# design.net
KiCad netlist of a schematic drawn in EasyEDA Pro
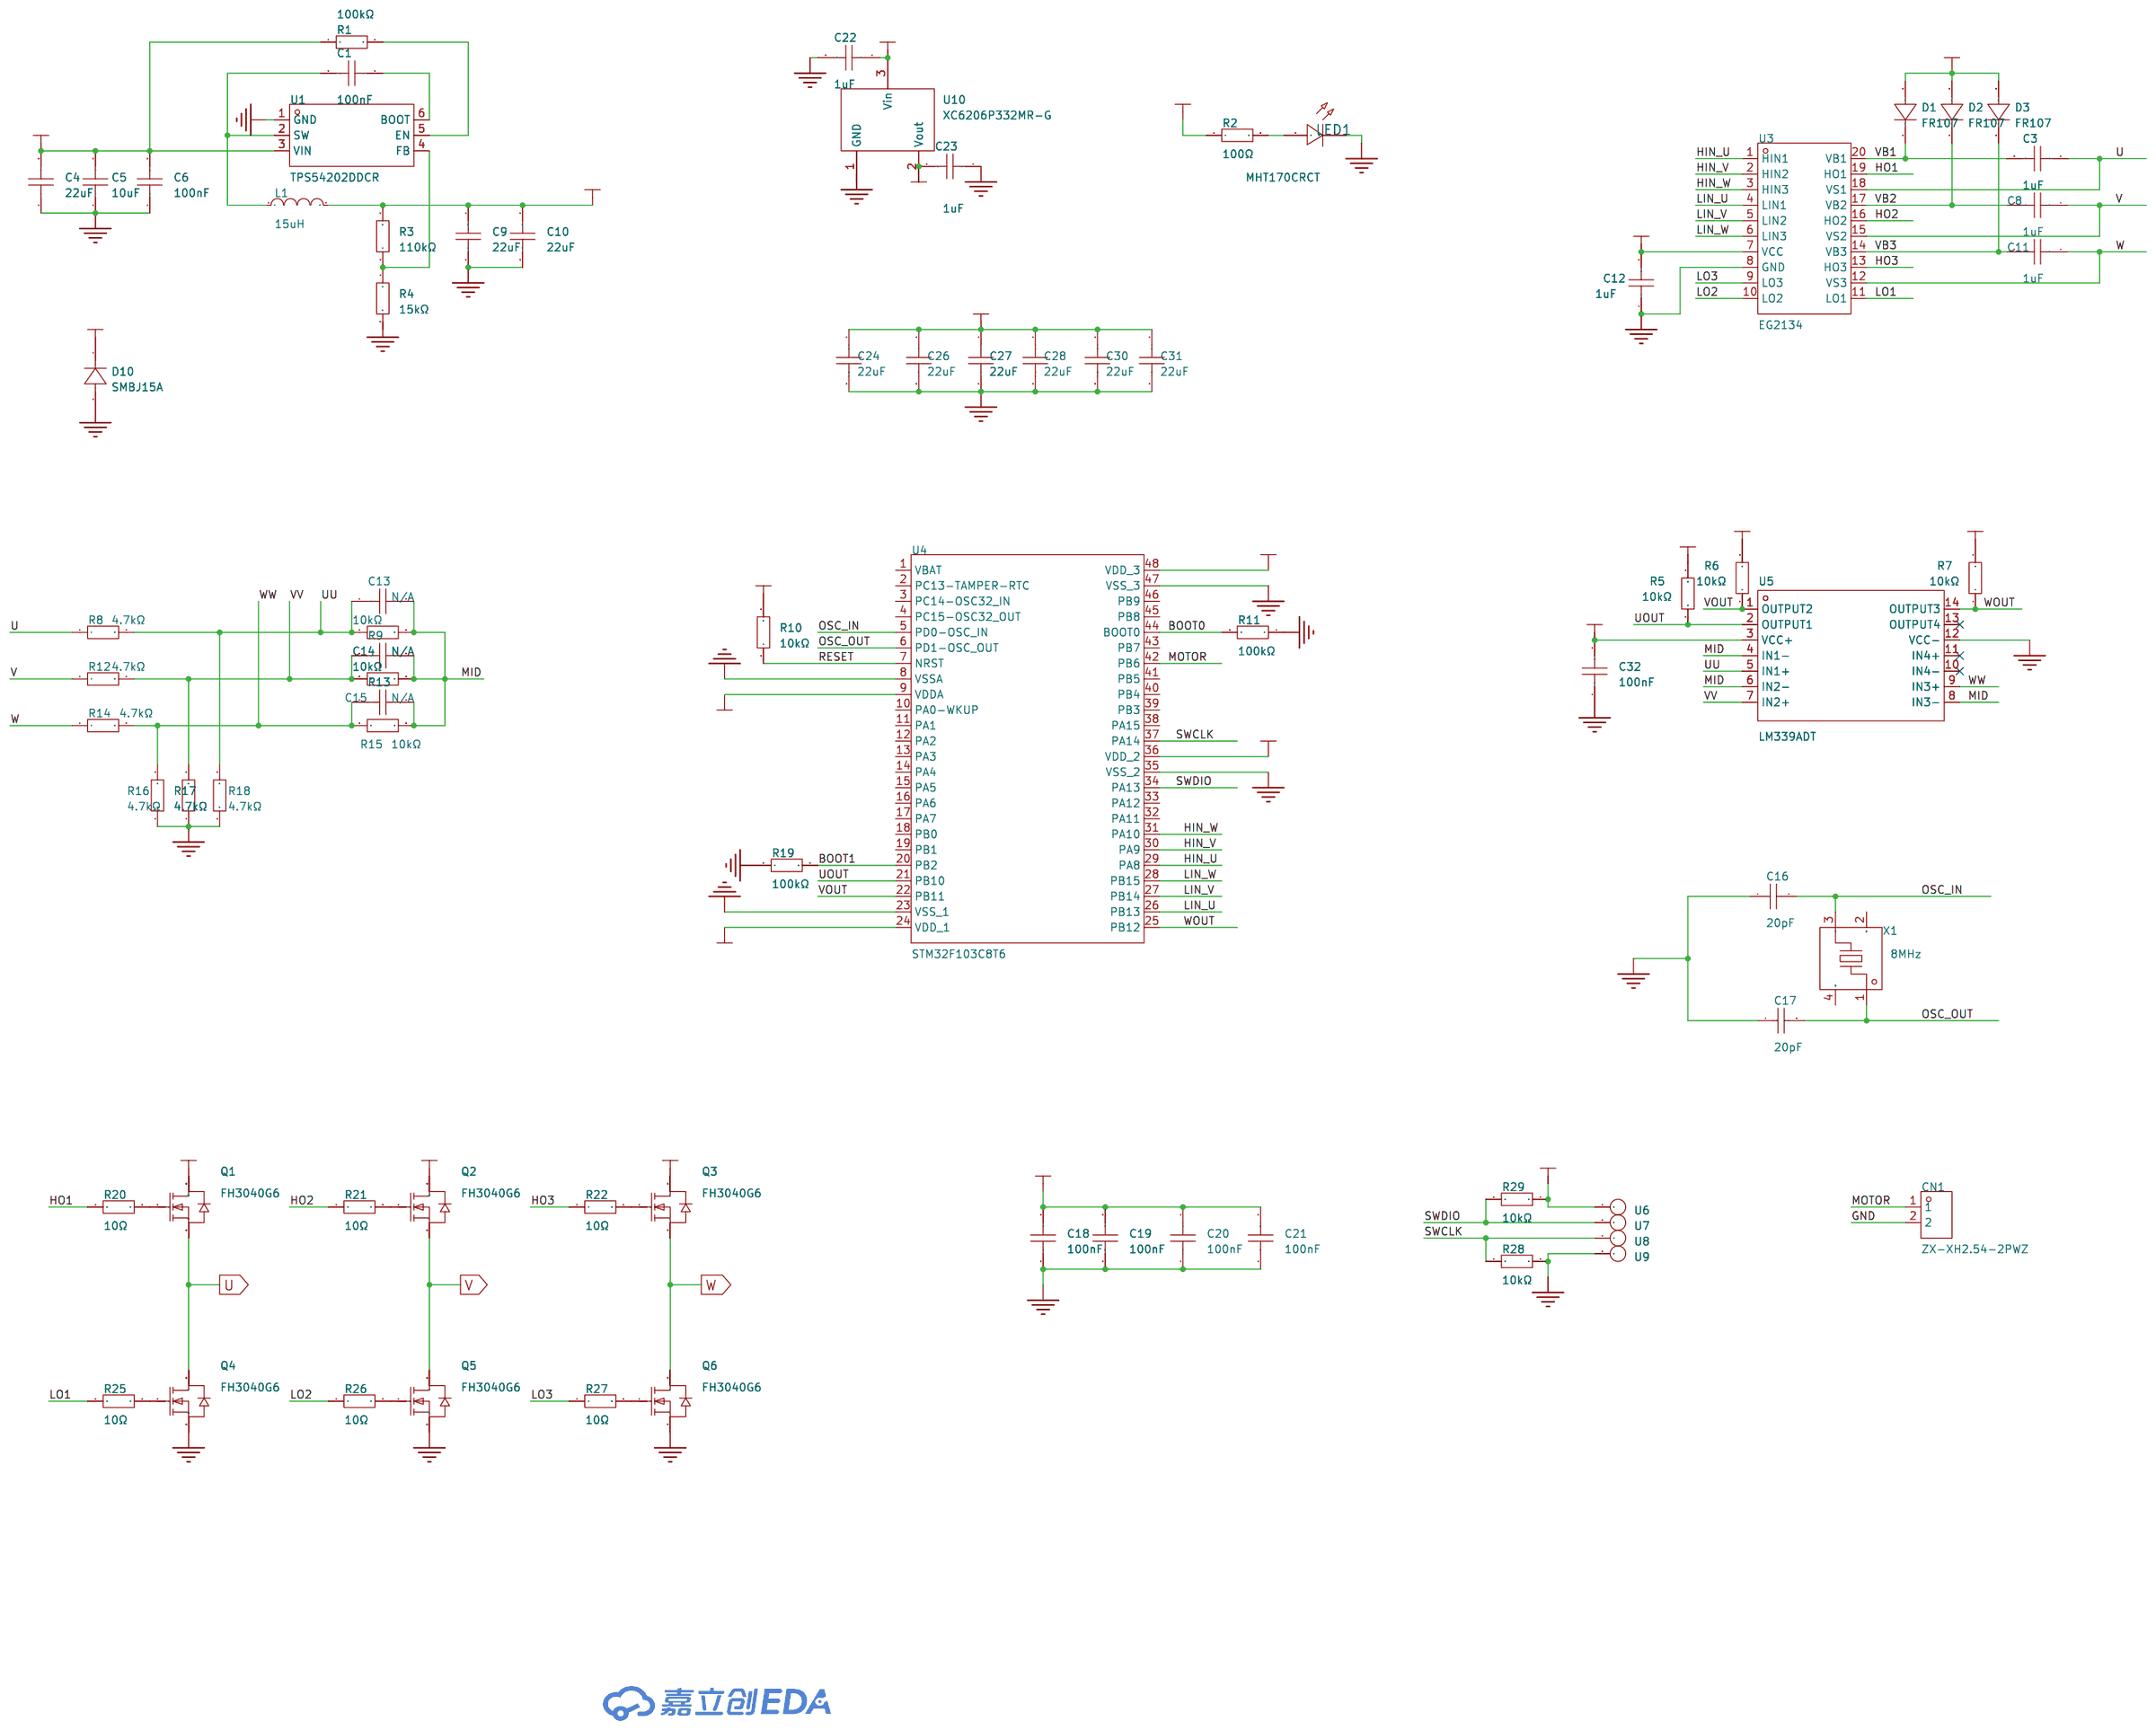
[diagram p0: schematic sheet]

(export (version "E")
  (design (tool "Eeschema 10.0.6"))
  (components
    (comp (ref "C1")
      (value "100nF")
      (footprint "easyedapro:C0603")
      (fields
        (field (name "Manufacturer Part") "CGA0603X7R104K500JT")
        (field (name "Manufacturer") "HRE(芯声)")
      )
      (libsource (lib "easyedapro") (part "CapAcitance"))
    )
    (comp (ref "C3")
      (value "1uF")
      (footprint "easyedapro:C0603")
      (description "容值:1uF;精度:±10%;额定电压:50V;材质(温度系数):X5R;")
      (fields
        (field (name "Manufacturer Part") "CL10A105KB8NNNC")
        (field (name "Manufacturer") "SAMSUNG(三星)")
      )
      (libsource (lib "easyedapro") (part "CL10A105KB8NNNC"))
    )
    (comp (ref "C4")
      (value "22uF")
      (footprint "easyedapro:C0805")
      (description "容值:22uF;精度:±20%;额定电压:25V;材质(温度系数):X5R;")
      (fields
        (field (name "Manufacturer Part") "CL21A226MAYNNNE")
        (field (name "Manufacturer") "SAMSUNG(三星)")
      )
      (libsource (lib "easyedapro") (part "CL21A226MAYNNNE"))
    )
    (comp (ref "C5")
      (value "10uF")
      (footprint "easyedapro:C0805")
      (description "容值:10uF;精度:±10%;额定电压:25V;材质(温度系数):X5R;")
      (fields
        (field (name "Manufacturer Part") "CL21A106KAYNNNE")
        (field (name "Manufacturer") "SAMSUNG(三星)")
      )
      (libsource (lib "easyedapro") (part "CL21A106KAYNNNE"))
    )
    (comp (ref "C6")
      (value "100nF")
      (footprint "easyedapro:C0603")
      (fields
        (field (name "Manufacturer Part") "CGA0603X7R104K500JT")
        (field (name "Manufacturer") "HRE(芯声)")
      )
      (libsource (lib "easyedapro") (part "CapAcitance"))
    )
    (comp (ref "C8")
      (value "1uF")
      (footprint "easyedapro:C0603")
      (description "容值:1uF;精度:±10%;额定电压:50V;材质(温度系数):X5R;")
      (fields
        (field (name "Manufacturer Part") "CL10A105KB8NNNC")
        (field (name "Manufacturer") "SAMSUNG(三星)")
      )
      (libsource (lib "easyedapro") (part "CL10A105KB8NNNC"))
    )
    (comp (ref "C9")
      (value "22uF")
      (footprint "easyedapro:C0805")
      (description "容值:22uF;精度:±20%;额定电压:25V;材质(温度系数):X5R;")
      (fields
        (field (name "Manufacturer Part") "CL21A226MAYNNNE")
        (field (name "Manufacturer") "SAMSUNG(三星)")
      )
      (libsource (lib "easyedapro") (part "CL21A226MAYNNNE"))
    )
    (comp (ref "C10")
      (value "22uF")
      (footprint "easyedapro:C0805")
      (description "容值:22uF;精度:±20%;额定电压:25V;材质(温度系数):X5R;")
      (fields
        (field (name "Manufacturer Part") "CL21A226MAYNNNE")
        (field (name "Manufacturer") "SAMSUNG(三星)")
      )
      (libsource (lib "easyedapro") (part "CL21A226MAYNNNE"))
    )
    (comp (ref "C11")
      (value "1uF")
      (footprint "easyedapro:C0603")
      (description "容值:1uF;精度:±10%;额定电压:50V;材质(温度系数):X5R;")
      (fields
        (field (name "Manufacturer Part") "CL10A105KB8NNNC")
        (field (name "Manufacturer") "SAMSUNG(三星)")
      )
      (libsource (lib "easyedapro") (part "CL10A105KB8NNNC"))
    )
    (comp (ref "C12")
      (value "1uF")
      (footprint "easyedapro:C0603")
      (description "容值:1uF;精度:±10%;额定电压:50V;材质(温度系数):X5R;")
      (fields
        (field (name "Manufacturer Part") "CL10A105KB8NNNC")
        (field (name "Manufacturer") "SAMSUNG(三星)")
      )
      (libsource (lib "easyedapro") (part "CL10A105KB8NNNC"))
    )
    (comp (ref "C13")
      (value "N/A")
      (footprint "easyedapro:C0603")
      (libsource (lib "easyedapro") (part "CapAcitance"))
    )
    (comp (ref "C14")
      (value "N/A")
      (footprint "easyedapro:C0603")
      (libsource (lib "easyedapro") (part "CapAcitance"))
    )
    (comp (ref "C15")
      (value "N/A")
      (footprint "easyedapro:C0603")
      (libsource (lib "easyedapro") (part "CapAcitance"))
    )
    (comp (ref "C16")
      (value "20pF")
      (footprint "easyedapro:C0603")
      (description "容值:20pF;精度:±5%;额定电压:50V;材质(温度系数):NP0;")
      (fields
        (field (name "Manufacturer Part") "CC0603JRNPO9BN200")
        (field (name "Manufacturer") "YAGEO(国巨)")
      )
      (libsource (lib "easyedapro") (part "CC0603JRNPO9BN200"))
    )
    (comp (ref "C17")
      (value "20pF")
      (footprint "easyedapro:C0603")
      (description "容值:20pF;精度:±5%;额定电压:50V;材质(温度系数):NP0;")
      (fields
        (field (name "Manufacturer Part") "CC0603JRNPO9BN200")
        (field (name "Manufacturer") "YAGEO(国巨)")
      )
      (libsource (lib "easyedapro") (part "CC0603JRNPO9BN200"))
    )
    (comp (ref "C18")
      (value "100nF")
      (footprint "easyedapro:C0603")
      (fields
        (field (name "Manufacturer Part") "CGA0603X7R104K500JT")
        (field (name "Manufacturer") "HRE(芯声)")
      )
      (libsource (lib "easyedapro") (part "CapAcitance"))
    )
    (comp (ref "C19")
      (value "100nF")
      (footprint "easyedapro:C0603")
      (fields
        (field (name "Manufacturer Part") "CGA0603X7R104K500JT")
        (field (name "Manufacturer") "HRE(芯声)")
      )
      (libsource (lib "easyedapro") (part "CapAcitance"))
    )
    (comp (ref "C20")
      (value "100nF")
      (footprint "easyedapro:C0603")
      (fields
        (field (name "Manufacturer Part") "CGA0603X7R104K500JT")
        (field (name "Manufacturer") "HRE(芯声)")
      )
      (libsource (lib "easyedapro") (part "CapAcitance"))
    )
    (comp (ref "C21")
      (value "100nF")
      (footprint "easyedapro:C0603")
      (fields
        (field (name "Manufacturer Part") "CGA0603X7R104K500JT")
        (field (name "Manufacturer") "HRE(芯声)")
      )
      (libsource (lib "easyedapro") (part "CapAcitance"))
    )
    (comp (ref "C22")
      (value "1uF")
      (footprint "easyedapro:C0603")
      (description "容值:1uF;精度:±10%;额定电压:50V;材质(温度系数):X5R;")
      (fields
        (field (name "Manufacturer Part") "CL10A105KB8NNNC")
        (field (name "Manufacturer") "SAMSUNG(三星)")
      )
      (libsource (lib "easyedapro") (part "CL10A105KB8NNNC"))
    )
    (comp (ref "C23")
      (value "1uF")
      (footprint "easyedapro:C0603")
      (description "容值:1uF;精度:±10%;额定电压:50V;材质(温度系数):X5R;")
      (fields
        (field (name "Manufacturer Part") "CL10A105KB8NNNC")
        (field (name "Manufacturer") "SAMSUNG(三星)")
      )
      (libsource (lib "easyedapro") (part "CL10A105KB8NNNC"))
    )
    (comp (ref "C24")
      (value "22uF")
      (footprint "easyedapro:C0805")
      (description "容值:22uF;精度:±20%;额定电压:25V;材质(温度系数):X5R;")
      (fields
        (field (name "Manufacturer Part") "CL21A226MAYNNNE")
        (field (name "Manufacturer") "SAMSUNG(三星)")
      )
      (libsource (lib "easyedapro") (part "CL21A226MAYNNNE"))
    )
    (comp (ref "C26")
      (value "22uF")
      (footprint "easyedapro:C0805")
      (description "容值:22uF;精度:±20%;额定电压:25V;材质(温度系数):X5R;")
      (fields
        (field (name "Manufacturer Part") "CL21A226MAYNNNE")
        (field (name "Manufacturer") "SAMSUNG(三星)")
      )
      (libsource (lib "easyedapro") (part "CL21A226MAYNNNE"))
    )
    (comp (ref "C27")
      (value "22uF")
      (footprint "easyedapro:C0805")
      (description "容值:22uF;精度:±20%;额定电压:25V;材质(温度系数):X5R;")
      (fields
        (field (name "Manufacturer Part") "CL21A226MAYNNNE")
        (field (name "Manufacturer") "SAMSUNG(三星)")
      )
      (libsource (lib "easyedapro") (part "CL21A226MAYNNNE"))
    )
    (comp (ref "C28")
      (value "22uF")
      (footprint "easyedapro:C0805")
      (description "容值:22uF;精度:±20%;额定电压:25V;材质(温度系数):X5R;")
      (fields
        (field (name "Manufacturer Part") "CL21A226MAYNNNE")
        (field (name "Manufacturer") "SAMSUNG(三星)")
      )
      (libsource (lib "easyedapro") (part "CL21A226MAYNNNE"))
    )
    (comp (ref "C30")
      (value "22uF")
      (footprint "easyedapro:C0805")
      (description "容值:22uF;精度:±20%;额定电压:25V;材质(温度系数):X5R;")
      (fields
        (field (name "Manufacturer Part") "CL21A226MAYNNNE")
        (field (name "Manufacturer") "SAMSUNG(三星)")
      )
      (libsource (lib "easyedapro") (part "CL21A226MAYNNNE"))
    )
    (comp (ref "C31")
      (value "22uF")
      (footprint "easyedapro:C0805")
      (description "容值:22uF;精度:±20%;额定电压:25V;材质(温度系数):X5R;")
      (fields
        (field (name "Manufacturer Part") "CL21A226MAYNNNE")
        (field (name "Manufacturer") "SAMSUNG(三星)")
      )
      (libsource (lib "easyedapro") (part "CL21A226MAYNNNE"))
    )
    (comp (ref "C32")
      (value "100nF")
      (footprint "easyedapro:C0603")
      (fields
        (field (name "Manufacturer Part") "CGA0603X7R104K500JT")
        (field (name "Manufacturer") "HRE(芯声)")
      )
      (libsource (lib "easyedapro") (part "CapAcitance"))
    )
    (comp (ref "CN1")
      (value "ZX-XH2.54-2PWZ")
      (footprint "easyedapro:CONN-TH_2P-P2.50_ZX-XH2.54-2PWZ")
      (fields (field (name "Manufacturer") "Megastar(兆星)"))
      (libsource (lib "easyedapro") (part "ZX-XH2.54-2PWZ"))
    )
    (comp (ref "D1")
      (value "FR107")
      (footprint "easyedapro:SOD-123FL_L2.7-W1.8-LS3.8-RD")
      (description "二极管配置:独立式;正向压降(Vf):1.3V@1A;直流反向耐压(Vr):1kV;整流电流:1A;反向恢复时间(trr):500ns;")
      (fields (field (name "Manufacturer") "Slkor(萨科微)"))
      (libsource (lib "easyedapro") (part "FR107_C2760867"))
    )
    (comp (ref "D2")
      (value "FR107")
      (footprint "easyedapro:SOD-123FL_L2.7-W1.8-LS3.8-RD")
      (description "二极管配置:独立式;正向压降(Vf):1.3V@1A;直流反向耐压(Vr):1kV;整流电流:1A;反向恢复时间(trr):500ns;")
      (fields (field (name "Manufacturer") "Slkor(萨科微)"))
      (libsource (lib "easyedapro") (part "FR107_C2760867"))
    )
    (comp (ref "D3")
      (value "FR107")
      (footprint "easyedapro:SOD-123FL_L2.7-W1.8-LS3.8-RD")
      (description "二极管配置:独立式;正向压降(Vf):1.3V@1A;直流反向耐压(Vr):1kV;整流电流:1A;反向恢复时间(trr):500ns;")
      (fields (field (name "Manufacturer") "Slkor(萨科微)"))
      (libsource (lib "easyedapro") (part "FR107_C2760867"))
    )
    (comp (ref "D10")
      (value "SMBJ15A")
      (footprint "easyedapro:SMB_L4.3-W3.6-LS5.3-RD")
      (description "极性:单向;反向截止电压(Vrwm):15V;钳位电压:24.4V;峰值脉冲电流(Ipp):24.59A;峰值脉冲功率(Ppp):600W;击穿电压:18.5V;")
      (fields (field (name "Manufacturer") "宏嘉诚"))
      (libsource (lib "easyedapro") (part "SMBJ15A_C19077569"))
    )
    (comp (ref "L1")
      (value "15uH")
      (footprint "easyedapro:IND-SMD_L7.0-W6.6_FXL0630")
      (description "电感值:15uH;精度:±20%;额定电流:3A;饱和电流(Isat):4.5A;类型:一体成型电感;")
      (fields (field (name "Manufacturer Part") "FXL0630-150-M") (field (name "Manufacturer") "cjiang(长江微电)"))
      (libsource (lib "easyedapro") (part "FXL0630-150-M"))
    )
    (comp (ref "LED1")
      (value "MHT170CRCT")
      (fields (field (name "Manufacturer") "MEIHUA(美华)"))
      (libsource (lib "easyedapro") (part "LED_R"))
    )
    (comp (ref "Q1")
      (value "FH3040G6")
      (footprint "easyedapro:DFN-8_L3.3-W3.0-P0.65-LS3.3-BL-EP")
      (description "类型:1个N沟道;漏源电压(Vdss):30V;连续漏极电流(Id):40A;导通电阻(RDS(on)):-;耗散功率(Pd):35W;阈值电压(Vgs(th)):1.6V;")
      (fields (field (name "Manufacturer") "鑫飞宏"))
      (libsource (lib "easyedapro") (part "FH3040G6"))
    )
    (comp (ref "Q2")
      (value "FH3040G6")
      (footprint "easyedapro:DFN-8_L3.3-W3.0-P0.65-LS3.3-BL-EP")
      (description "类型:1个N沟道;漏源电压(Vdss):30V;连续漏极电流(Id):40A;导通电阻(RDS(on)):-;耗散功率(Pd):35W;阈值电压(Vgs(th)):1.6V;")
      (fields (field (name "Manufacturer") "鑫飞宏"))
      (libsource (lib "easyedapro") (part "FH3040G6"))
    )
    (comp (ref "Q3")
      (value "FH3040G6")
      (footprint "easyedapro:DFN-8_L3.3-W3.0-P0.65-LS3.3-BL-EP")
      (description "类型:1个N沟道;漏源电压(Vdss):30V;连续漏极电流(Id):40A;导通电阻(RDS(on)):-;耗散功率(Pd):35W;阈值电压(Vgs(th)):1.6V;")
      (fields (field (name "Manufacturer") "鑫飞宏"))
      (libsource (lib "easyedapro") (part "FH3040G6"))
    )
    (comp (ref "Q4")
      (value "FH3040G6")
      (footprint "easyedapro:DFN-8_L3.3-W3.0-P0.65-LS3.3-BL-EP")
      (description "类型:1个N沟道;漏源电压(Vdss):30V;连续漏极电流(Id):40A;导通电阻(RDS(on)):-;耗散功率(Pd):35W;阈值电压(Vgs(th)):1.6V;")
      (fields (field (name "Manufacturer") "鑫飞宏"))
      (libsource (lib "easyedapro") (part "FH3040G6"))
    )
    (comp (ref "Q5")
      (value "FH3040G6")
      (footprint "easyedapro:DFN-8_L3.3-W3.0-P0.65-LS3.3-BL-EP")
      (description "类型:1个N沟道;漏源电压(Vdss):30V;连续漏极电流(Id):40A;导通电阻(RDS(on)):-;耗散功率(Pd):35W;阈值电压(Vgs(th)):1.6V;")
      (fields (field (name "Manufacturer") "鑫飞宏"))
      (libsource (lib "easyedapro") (part "FH3040G6"))
    )
    (comp (ref "Q6")
      (value "FH3040G6")
      (footprint "easyedapro:DFN-8_L3.3-W3.0-P0.65-LS3.3-BL-EP")
      (description "类型:1个N沟道;漏源电压(Vdss):30V;连续漏极电流(Id):40A;导通电阻(RDS(on)):-;耗散功率(Pd):35W;阈值电压(Vgs(th)):1.6V;")
      (fields (field (name "Manufacturer") "鑫飞宏"))
      (libsource (lib "easyedapro") (part "FH3040G6"))
    )
    (comp (ref "R1")
      (value "100kΩ")
      (fields (field (name "Manufacturer Part") "RT0603BRD07100KL") (field (name "Manufacturer") "YAGEO(国巨)"))
      (libsource (lib "easyedapro") (part "电阻"))
    )
    (comp (ref "R2")
      (value "100Ω")
      (fields (field (name "Manufacturer Part") "RC0603FR-07100RL") (field (name "Manufacturer") "YAGEO(国巨)"))
      (libsource (lib "easyedapro") (part "电阻"))
    )
    (comp (ref "R3")
      (value "110kΩ")
      (footprint "easyedapro:R0603")
      (description "电阻类型:厚膜电阻;阻值:110kΩ;精度:±1%;功率:100mW;最大工作电压:75V;温度系数:±100ppm/°C;")
      (fields (field (name "Manufacturer Part") "RC0603FR-07110KL") (field (name "Manufacturer") "YAGEO(国巨)"))
      (libsource (lib "easyedapro") (part "RC0603FR-07110KL"))
    )
    (comp (ref "R4")
      (value "15kΩ")
      (footprint "easyedapro:R0603")
      (description "电阻类型:厚膜电阻;阻值:15kΩ;精度:±1%;功率:100mW;最大工作电压:75V;温度系数:±100ppm/°C;")
      (fields (field (name "Manufacturer Part") "RC0603FR-0715KL") (field (name "Manufacturer") "YAGEO(国巨)"))
      (libsource (lib "easyedapro") (part "RC0603FR-0715KL"))
    )
    (comp (ref "R5")
      (value "10kΩ")
      (fields
        (field (name "Manufacturer Part") "0603WAF1002T5E")
        (field (name "Manufacturer") "UNI-ROYAL(厚声)")
      )
      (libsource (lib "easyedapro") (part "电阻"))
    )
    (comp (ref "R6")
      (value "10kΩ")
      (fields
        (field (name "Manufacturer Part") "0603WAF1002T5E")
        (field (name "Manufacturer") "UNI-ROYAL(厚声)")
      )
      (libsource (lib "easyedapro") (part "电阻"))
    )
    (comp (ref "R7")
      (value "10kΩ")
      (fields
        (field (name "Manufacturer Part") "0603WAF1002T5E")
        (field (name "Manufacturer") "UNI-ROYAL(厚声)")
      )
      (libsource (lib "easyedapro") (part "电阻"))
    )
    (comp (ref "R8")
      (value "4.7kΩ")
      (fields
        (field (name "Manufacturer Part") "0603WAF4701T5E")
        (field (name "Manufacturer") "UNI-ROYAL(厚声)")
      )
      (libsource (lib "easyedapro") (part "电阻"))
    )
    (comp (ref "R9")
      (value "10kΩ")
      (fields
        (field (name "Manufacturer Part") "0603WAF1002T5E")
        (field (name "Manufacturer") "UNI-ROYAL(厚声)")
      )
      (libsource (lib "easyedapro") (part "电阻"))
    )
    (comp (ref "R10")
      (value "10kΩ")
      (fields
        (field (name "Manufacturer Part") "0603WAF1002T5E")
        (field (name "Manufacturer") "UNI-ROYAL(厚声)")
      )
      (libsource (lib "easyedapro") (part "电阻"))
    )
    (comp (ref "R11")
      (value "100kΩ")
      (fields (field (name "Manufacturer Part") "RT0603BRD07100KL") (field (name "Manufacturer") "YAGEO(国巨)"))
      (libsource (lib "easyedapro") (part "电阻"))
    )
    (comp (ref "R12")
      (value "4.7kΩ")
      (fields
        (field (name "Manufacturer Part") "0603WAF4701T5E")
        (field (name "Manufacturer") "UNI-ROYAL(厚声)")
      )
      (libsource (lib "easyedapro") (part "电阻"))
    )
    (comp (ref "R13")
      (value "10kΩ")
      (fields
        (field (name "Manufacturer Part") "0603WAF1002T5E")
        (field (name "Manufacturer") "UNI-ROYAL(厚声)")
      )
      (libsource (lib "easyedapro") (part "电阻"))
    )
    (comp (ref "R14")
      (value "4.7kΩ")
      (fields
        (field (name "Manufacturer Part") "0603WAF4701T5E")
        (field (name "Manufacturer") "UNI-ROYAL(厚声)")
      )
      (libsource (lib "easyedapro") (part "电阻"))
    )
    (comp (ref "R15")
      (value "10kΩ")
      (fields
        (field (name "Manufacturer Part") "0603WAF1002T5E")
        (field (name "Manufacturer") "UNI-ROYAL(厚声)")
      )
      (libsource (lib "easyedapro") (part "电阻"))
    )
    (comp (ref "R16")
      (value "4.7kΩ")
      (fields
        (field (name "Manufacturer Part") "0603WAF4701T5E")
        (field (name "Manufacturer") "UNI-ROYAL(厚声)")
      )
      (libsource (lib "easyedapro") (part "电阻"))
    )
    (comp (ref "R17")
      (value "4.7kΩ")
      (fields
        (field (name "Manufacturer Part") "0603WAF4701T5E")
        (field (name "Manufacturer") "UNI-ROYAL(厚声)")
      )
      (libsource (lib "easyedapro") (part "电阻"))
    )
    (comp (ref "R18")
      (value "4.7kΩ")
      (fields
        (field (name "Manufacturer Part") "0603WAF4701T5E")
        (field (name "Manufacturer") "UNI-ROYAL(厚声)")
      )
      (libsource (lib "easyedapro") (part "电阻"))
    )
    (comp (ref "R19")
      (value "100kΩ")
      (fields (field (name "Manufacturer Part") "RT0603BRD07100KL") (field (name "Manufacturer") "YAGEO(国巨)"))
      (libsource (lib "easyedapro") (part "电阻"))
    )
    (comp (ref "R20")
      (value "10Ω")
      (footprint "easyedapro:R0603")
      (description "电阻类型:厚膜电阻;阻值:20Ω;精度:±1%;功率:100mW;最大工作电压:75V;温度系数:±100ppm/°C;")
      (fields (field (name "Manufacturer Part") "RC0603FR-0710RL") (field (name "Manufacturer") "YAGEO(国巨)"))
      (libsource (lib "easyedapro") (part "0603WAF200JT5E"))
    )
    (comp (ref "R21")
      (value "10Ω")
      (footprint "easyedapro:R0603")
      (description "电阻类型:厚膜电阻;阻值:20Ω;精度:±1%;功率:100mW;最大工作电压:75V;温度系数:±100ppm/°C;")
      (fields (field (name "Manufacturer Part") "RC0603FR-0710RL") (field (name "Manufacturer") "YAGEO(国巨)"))
      (libsource (lib "easyedapro") (part "0603WAF200JT5E"))
    )
    (comp (ref "R22")
      (value "10Ω")
      (footprint "easyedapro:R0603")
      (description "电阻类型:厚膜电阻;阻值:20Ω;精度:±1%;功率:100mW;最大工作电压:75V;温度系数:±100ppm/°C;")
      (fields (field (name "Manufacturer Part") "RC0603FR-0710RL") (field (name "Manufacturer") "YAGEO(国巨)"))
      (libsource (lib "easyedapro") (part "0603WAF200JT5E"))
    )
    (comp (ref "R25")
      (value "10Ω")
      (footprint "easyedapro:R0603")
      (description "电阻类型:厚膜电阻;阻值:20Ω;精度:±1%;功率:100mW;最大工作电压:75V;温度系数:±100ppm/°C;")
      (fields (field (name "Manufacturer Part") "RC0603FR-0710RL") (field (name "Manufacturer") "YAGEO(国巨)"))
      (libsource (lib "easyedapro") (part "0603WAF200JT5E"))
    )
    (comp (ref "R26")
      (value "10Ω")
      (footprint "easyedapro:R0603")
      (description "电阻类型:厚膜电阻;阻值:20Ω;精度:±1%;功率:100mW;最大工作电压:75V;温度系数:±100ppm/°C;")
      (fields (field (name "Manufacturer Part") "RC0603FR-0710RL") (field (name "Manufacturer") "YAGEO(国巨)"))
      (libsource (lib "easyedapro") (part "0603WAF200JT5E"))
    )
    (comp (ref "R27")
      (value "10Ω")
      (footprint "easyedapro:R0603")
      (description "电阻类型:厚膜电阻;阻值:20Ω;精度:±1%;功率:100mW;最大工作电压:75V;温度系数:±100ppm/°C;")
      (fields (field (name "Manufacturer Part") "RC0603FR-0710RL") (field (name "Manufacturer") "YAGEO(国巨)"))
      (libsource (lib "easyedapro") (part "0603WAF200JT5E"))
    )
    (comp (ref "R28")
      (value "10kΩ")
      (fields
        (field (name "Manufacturer Part") "0603WAF1002T5E")
        (field (name "Manufacturer") "UNI-ROYAL(厚声)")
      )
      (libsource (lib "easyedapro") (part "电阻"))
    )
    (comp (ref "R29")
      (value "10kΩ")
      (fields
        (field (name "Manufacturer Part") "0603WAF1002T5E")
        (field (name "Manufacturer") "UNI-ROYAL(厚声)")
      )
      (libsource (lib "easyedapro") (part "电阻"))
    )
    (comp (ref "U1")
      (value "TPS54202DDCR")
      (footprint "easyedapro:SOT-23-6_L2.9-W1.6-P0.95-LS2.8-BL")
      (description "功能类型:降压型;输出类型:可调;工作电压:4.5V~28V;输出电压:-;输出电流:2A;")
      (fields (field (name "Manufacturer") "TI(德州仪器)"))
      (libsource (lib "easyedapro") (part "TPS54202DDCR"))
    )
    (comp (ref "U3")
      (value "EG2134")
      (footprint "easyedapro:TSSOP-20_L6.5-W4.4-P0.65-LS6.4-BL")
      (fields (field (name "Manufacturer") "EG(屹晶微)"))
      (libsource (lib "easyedapro") (part "EG2134_C480661"))
    )
    (comp (ref "U4")
      (value "STM32F103C8T6")
      (footprint "easyedapro:LQFP-48_L7.0-W7.0-P0.50-LS9.0-BL")
      (description "CPU内核:ARM-M3;CPU最大主频:72MHz;应用领域:-;")
      (fields (field (name "Manufacturer") "ST(意法半导体)"))
      (libsource (lib "easyedapro") (part "STM32F103C8T6"))
    )
    (comp (ref "U5")
      (value "LM339ADT")
      (footprint "easyedapro:SOIC-14_L8.7-W3.9-P1.27-LS6.0-BL")
      (description "输入失调电压(Vos):2mV;输入偏置电流(Ib):100nA;")
      (fields (field (name "Manufacturer") "ST(意法半导体)"))
      (libsource (lib "easyedapro") (part "LM339ADT"))
    )
    (comp (ref "U6") (value "~") (footprint "easyedapro:触点") (libsource (lib "easyedapro") (part "触点")))
    (comp (ref "U7") (value "~") (footprint "easyedapro:触点") (libsource (lib "easyedapro") (part "触点")))
    (comp (ref "U8") (value "~") (footprint "easyedapro:触点") (libsource (lib "easyedapro") (part "触点")))
    (comp (ref "U9") (value "~") (footprint "easyedapro:触点") (libsource (lib "easyedapro") (part "触点")))
    (comp (ref "U10")
      (value "XC6206P332MR-G")
      (footprint "easyedapro:SOT-23-3_L2.9-W1.6-P1.90-LS2.8-BR")
      (description "输出类型:固定;最大输入电压:6V;输出电压:3.3V;最大输出电流:200mA;电源纹波抑制比(PSRR):-;输出极性:正极;")
      (fields (field (name "Manufacturer") "TOREX(特瑞仕)"))
      (libsource (lib "easyedapro") (part "XC6206P332MR"))
    )
    (comp (ref "X1")
      (value "8MHz")
      (footprint "easyedapro:CRYSTAL-SMD_4P-L3.2-W2.5-BL")
      (description "晶振类型:贴片晶振;频率:8MHz;常温频差:±10ppm;负载电容:20pF;频率稳定度:±20ppm;")
      (fields (field (name "Manufacturer Part") "X32258MSB4SI") (field (name "Manufacturer") "YXC(扬兴晶振)"))
      (libsource (lib "easyedapro") (part "X32258MSB4SI"))
    )
  )
  (nets
    (net (code "1") (name "/BOOT0") (class "Default")
      (node (ref "R11") (pin "2") (pinfunction "2_2") (pintype "input"))
      (node (ref "U4") (pin "44") (pinfunction "BOOT0_44") (pintype "unspecified"))
    )
    (net (code "2") (name "/BOOT1") (class "Default")
      (node (ref "R19") (pin "2") (pinfunction "2_2") (pintype "input"))
      (node (ref "U4") (pin "20") (pinfunction "PB2_20") (pintype "unspecified"))
    )
    (net (code "3") (name "/HIN_U") (class "Default")
      (node (ref "U3") (pin "1") (pinfunction "HIN1_1") (pintype "unspecified"))
      (node (ref "U4") (pin "29") (pinfunction "PA8_29") (pintype "unspecified"))
    )
    (net (code "4") (name "/HIN_V") (class "Default")
      (node (ref "U3") (pin "2") (pinfunction "HIN2_2") (pintype "unspecified"))
      (node (ref "U4") (pin "30") (pinfunction "PA9_30") (pintype "unspecified"))
    )
    (net (code "5") (name "/HIN_W") (class "Default")
      (node (ref "U3") (pin "3") (pinfunction "HIN3_3") (pintype "unspecified"))
      (node (ref "U4") (pin "31") (pinfunction "PA10_31") (pintype "unspecified"))
    )
    (net (code "6") (name "/HO1") (class "Default")
      (node (ref "R20") (pin "1") (pinfunction "1_1") (pintype "input"))
      (node (ref "U3") (pin "19") (pinfunction "HO1_19") (pintype "unspecified"))
    )
    (net (code "7") (name "/HO2") (class "Default")
      (node (ref "R21") (pin "1") (pinfunction "1_1") (pintype "input"))
      (node (ref "U3") (pin "16") (pinfunction "HO2_16") (pintype "unspecified"))
    )
    (net (code "8") (name "/HO3") (class "Default")
      (node (ref "R22") (pin "1") (pinfunction "1_1") (pintype "input"))
      (node (ref "U3") (pin "13") (pinfunction "HO3_13") (pintype "unspecified"))
    )
    (net (code "9") (name "/LIN_U") (class "Default")
      (node (ref "U3") (pin "4") (pinfunction "LIN1_4") (pintype "unspecified"))
      (node (ref "U4") (pin "26") (pinfunction "PB13_26") (pintype "unspecified"))
    )
    (net (code "10") (name "/LIN_V") (class "Default")
      (node (ref "U3") (pin "5") (pinfunction "LIN2_5") (pintype "unspecified"))
      (node (ref "U4") (pin "27") (pinfunction "PB14_27") (pintype "unspecified"))
    )
    (net (code "11") (name "/LIN_W") (class "Default")
      (node (ref "U3") (pin "6") (pinfunction "LIN3_6") (pintype "unspecified"))
      (node (ref "U4") (pin "28") (pinfunction "PB15_28") (pintype "unspecified"))
    )
    (net (code "12") (name "/LO1") (class "Default")
      (node (ref "R25") (pin "1") (pinfunction "1_1") (pintype "input"))
      (node (ref "U3") (pin "11") (pinfunction "LO1_11") (pintype "unspecified"))
    )
    (net (code "13") (name "/LO2") (class "Default")
      (node (ref "R26") (pin "1") (pinfunction "1_1") (pintype "input"))
      (node (ref "U3") (pin "10") (pinfunction "LO2_10") (pintype "unspecified"))
    )
    (net (code "14") (name "/LO3") (class "Default")
      (node (ref "R27") (pin "1") (pinfunction "1_1") (pintype "input"))
      (node (ref "U3") (pin "9") (pinfunction "LO3_9") (pintype "unspecified"))
    )
    (net (code "15") (name "/MID") (class "Default")
      (node (ref "C13") (pin "2") (pinfunction "2_2") (pintype "input"))
      (node (ref "C14") (pin "2") (pinfunction "2_2") (pintype "input"))
      (node (ref "C15") (pin "2") (pinfunction "2_2") (pintype "input"))
      (node (ref "R13") (pin "2") (pinfunction "2_2") (pintype "input"))
      (node (ref "R15") (pin "2") (pinfunction "2_2") (pintype "input"))
      (node (ref "R9") (pin "2") (pinfunction "2_2") (pintype "input"))
      (node (ref "U5") (pin "4") (pinfunction "IN1-_4") (pintype "unspecified"))
      (node (ref "U5") (pin "6") (pinfunction "IN2-_6") (pintype "unspecified"))
      (node (ref "U5") (pin "8") (pinfunction "IN3-_8") (pintype "unspecified"))
    )
    (net (code "16") (name "/MOTOR") (class "Default")
      (node (ref "CN1") (pin "1") (pinfunction "1_1") (pintype "unspecified"))
      (node (ref "U4") (pin "42") (pinfunction "PB6_42") (pintype "unspecified"))
    )
    (net (code "17") (name "/OSC_IN") (class "Default")
      (node (ref "C16") (pin "2") (pinfunction "2_2") (pintype "input"))
      (node (ref "U4") (pin "5") (pinfunction "PD0-OSC_IN_5") (pintype "unspecified"))
      (node (ref "X1") (pin "3") (pinfunction "3_3") (pintype "input"))
    )
    (net (code "18") (name "/OSC_OUT") (class "Default")
      (node (ref "C17") (pin "2") (pinfunction "2_2") (pintype "input"))
      (node (ref "U4") (pin "6") (pinfunction "PD1-OSC_OUT_6") (pintype "unspecified"))
      (node (ref "X1") (pin "1") (pinfunction "1_1") (pintype "input"))
    )
    (net (code "19") (name "/RESET") (class "Default")
      (node (ref "R10") (pin "1") (pinfunction "1_1") (pintype "input"))
      (node (ref "U4") (pin "7") (pinfunction "NRST_7") (pintype "unspecified"))
    )
    (net (code "20") (name "/SWCLK") (class "Default")
      (node (ref "R28") (pin "2") (pinfunction "2_2") (pintype "input"))
      (node (ref "U4") (pin "37") (pinfunction "PA14_37") (pintype "unspecified"))
      (node (ref "U8") (pin "1") (pinfunction "1_1") (pintype "input"))
    )
    (net (code "21") (name "/SWDIO") (class "Default")
      (node (ref "R29") (pin "2") (pinfunction "2_2") (pintype "input"))
      (node (ref "U4") (pin "34") (pinfunction "PA13_34") (pintype "unspecified"))
      (node (ref "U7") (pin "1") (pinfunction "1_1") (pintype "input"))
    )
    (net (code "22") (name "/UOUT") (class "Default")
      (node (ref "R5") (pin "1") (pinfunction "1_1") (pintype "input"))
      (node (ref "U4") (pin "21") (pinfunction "PB10_21") (pintype "unspecified"))
      (node (ref "U5") (pin "2") (pinfunction "OUTPUT1_2") (pintype "unspecified"))
    )
    (net (code "23") (name "/UU") (class "Default")
      (node (ref "C13") (pin "1") (pinfunction "1_1") (pintype "input"))
      (node (ref "R18") (pin "2") (pinfunction "2_2") (pintype "input"))
      (node (ref "R8") (pin "2") (pinfunction "2_2") (pintype "input"))
      (node (ref "R9") (pin "1") (pinfunction "1_1") (pintype "input"))
      (node (ref "U5") (pin "5") (pinfunction "IN1+_5") (pintype "unspecified"))
    )
    (net (code "24") (name "/VB1") (class "Default")
      (node (ref "C3") (pin "2") (pinfunction "2_2") (pintype "unspecified"))
      (node (ref "D1") (pin "1") (pinfunction "K_1") (pintype "unspecified"))
      (node (ref "U3") (pin "20") (pinfunction "VB1_20") (pintype "unspecified"))
    )
    (net (code "25") (name "/VB2") (class "Default")
      (node (ref "C8") (pin "2") (pinfunction "2_2") (pintype "unspecified"))
      (node (ref "D2") (pin "1") (pinfunction "K_1") (pintype "unspecified"))
      (node (ref "U3") (pin "17") (pinfunction "VB2_17") (pintype "unspecified"))
    )
    (net (code "26") (name "/VB3") (class "Default")
      (node (ref "C11") (pin "2") (pinfunction "2_2") (pintype "unspecified"))
      (node (ref "D3") (pin "1") (pinfunction "K_1") (pintype "unspecified"))
      (node (ref "U3") (pin "14") (pinfunction "VB3_14") (pintype "unspecified"))
    )
    (net (code "27") (name "/VOUT") (class "Default")
      (node (ref "R6") (pin "1") (pinfunction "1_1") (pintype "input"))
      (node (ref "U4") (pin "22") (pinfunction "PB11_22") (pintype "unspecified"))
      (node (ref "U5") (pin "1") (pinfunction "OUTPUT2_1") (pintype "unspecified"))
    )
    (net (code "28") (name "/VV") (class "Default")
      (node (ref "C14") (pin "1") (pinfunction "1_1") (pintype "input"))
      (node (ref "R12") (pin "2") (pinfunction "2_2") (pintype "input"))
      (node (ref "R13") (pin "1") (pinfunction "1_1") (pintype "input"))
      (node (ref "R17") (pin "2") (pinfunction "2_2") (pintype "input"))
      (node (ref "U5") (pin "7") (pinfunction "IN2+_7") (pintype "unspecified"))
    )
    (net (code "29") (name "/WOUT") (class "Default")
      (node (ref "R7") (pin "1") (pinfunction "1_1") (pintype "input"))
      (node (ref "U4") (pin "25") (pinfunction "PB12_25") (pintype "unspecified"))
      (node (ref "U5") (pin "14") (pinfunction "OUTPUT3_14") (pintype "unspecified"))
    )
    (net (code "30") (name "/WW") (class "Default")
      (node (ref "C15") (pin "1") (pinfunction "1_1") (pintype "input"))
      (node (ref "R14") (pin "2") (pinfunction "2_2") (pintype "input"))
      (node (ref "R15") (pin "1") (pinfunction "1_1") (pintype "input"))
      (node (ref "R16") (pin "2") (pinfunction "2_2") (pintype "input"))
      (node (ref "U5") (pin "9") (pinfunction "IN3+_9") (pintype "unspecified"))
    )
    (net (code "31") (name "GND") (class "Default")
      (node (ref "C10") (pin "2") (pinfunction "2_2") (pintype "unspecified"))
      (node (ref "C12") (pin "1") (pinfunction "1_1") (pintype "unspecified"))
      (node (ref "C16") (pin "1") (pinfunction "1_1") (pintype "input"))
      (node (ref "C17") (pin "1") (pinfunction "1_1") (pintype "input"))
      (node (ref "C18") (pin "1") (pinfunction "1_1") (pintype "input"))
      (node (ref "C19") (pin "1") (pinfunction "1_1") (pintype "input"))
      (node (ref "C20") (pin "1") (pinfunction "1_1") (pintype "input"))
      (node (ref "C21") (pin "1") (pinfunction "1_1") (pintype "input"))
      (node (ref "C22") (pin "2") (pinfunction "2_2") (pintype "unspecified"))
      (node (ref "C23") (pin "1") (pinfunction "1_1") (pintype "unspecified"))
      (node (ref "C24") (pin "2") (pinfunction "2_2") (pintype "unspecified"))
      (node (ref "C26") (pin "2") (pinfunction "2_2") (pintype "unspecified"))
      (node (ref "C27") (pin "2") (pinfunction "2_2") (pintype "unspecified"))
      (node (ref "C28") (pin "2") (pinfunction "2_2") (pintype "unspecified"))
      (node (ref "C30") (pin "2") (pinfunction "2_2") (pintype "unspecified"))
      (node (ref "C31") (pin "2") (pinfunction "2_2") (pintype "unspecified"))
      (node (ref "C32") (pin "1") (pinfunction "1_1") (pintype "input"))
      (node (ref "C4") (pin "1") (pinfunction "1_1") (pintype "unspecified"))
      (node (ref "C5") (pin "1") (pinfunction "1_1") (pintype "unspecified"))
      (node (ref "C6") (pin "1") (pinfunction "1_1") (pintype "input"))
      (node (ref "C9") (pin "2") (pinfunction "2_2") (pintype "unspecified"))
      (node (ref "CN1") (pin "2") (pinfunction "2_2") (pintype "unspecified"))
      (node (ref "D10") (pin "2") (pinfunction "A_2") (pintype "unspecified"))
      (node (ref "LED1") (pin "1") (pinfunction "C_1") (pintype "input"))
      (node (ref "Q4") (pin "1") (pinfunction "S_1") (pintype "unspecified"))
      (node (ref "Q4") (pin "2") (pinfunction "S_2") (pintype "unspecified"))
      (node (ref "Q4") (pin "3") (pinfunction "S_3") (pintype "unspecified"))
      (node (ref "Q5") (pin "1") (pinfunction "S_1") (pintype "unspecified"))
      (node (ref "Q5") (pin "2") (pinfunction "S_2") (pintype "unspecified"))
      (node (ref "Q5") (pin "3") (pinfunction "S_3") (pintype "unspecified"))
      (node (ref "Q6") (pin "1") (pinfunction "S_1") (pintype "unspecified"))
      (node (ref "Q6") (pin "2") (pinfunction "S_2") (pintype "unspecified"))
      (node (ref "Q6") (pin "3") (pinfunction "S_3") (pintype "unspecified"))
      (node (ref "R11") (pin "1") (pinfunction "1_1") (pintype "input"))
      (node (ref "R16") (pin "1") (pinfunction "1_1") (pintype "input"))
      (node (ref "R17") (pin "1") (pinfunction "1_1") (pintype "input"))
      (node (ref "R18") (pin "1") (pinfunction "1_1") (pintype "input"))
      (node (ref "R19") (pin "1") (pinfunction "1_1") (pintype "input"))
      (node (ref "R28") (pin "1") (pinfunction "1_1") (pintype "input"))
      (node (ref "R4") (pin "2") (pinfunction "2_2") (pintype "input"))
      (node (ref "U1") (pin "1") (pinfunction "GND_1") (pintype "unspecified"))
      (node (ref "U10") (pin "1") (pinfunction "GND_1") (pintype "unspecified"))
      (node (ref "U3") (pin "8") (pinfunction "GND_8") (pintype "unspecified"))
      (node (ref "U4") (pin "23") (pinfunction "VSS_1_23") (pintype "unspecified"))
      (node (ref "U4") (pin "35") (pinfunction "VSS_2_35") (pintype "unspecified"))
      (node (ref "U4") (pin "47") (pinfunction "VSS_3_47") (pintype "unspecified"))
      (node (ref "U4") (pin "8") (pinfunction "VSSA_8") (pintype "unspecified"))
      (node (ref "U5") (pin "12") (pinfunction "VCC-_12") (pintype "unspecified"))
      (node (ref "U9") (pin "1") (pinfunction "1_1") (pintype "input"))
    )
    (net (code "32") (name "Net-(LED1-A)") (class "Default")
      (node (ref "LED1") (pin "2") (pinfunction "A_2") (pintype "input"))
      (node (ref "R2") (pin "2") (pinfunction "2_2") (pintype "input"))
    )
    (net (code "33") (name "Net-(Q1-G)") (class "Default")
      (node (ref "Q1") (pin "4") (pinfunction "G_4") (pintype "unspecified"))
      (node (ref "R20") (pin "2") (pinfunction "2_2") (pintype "input"))
    )
    (net (code "34") (name "Net-(Q2-G)") (class "Default")
      (node (ref "Q2") (pin "4") (pinfunction "G_4") (pintype "unspecified"))
      (node (ref "R21") (pin "2") (pinfunction "2_2") (pintype "input"))
    )
    (net (code "35") (name "Net-(Q3-G)") (class "Default")
      (node (ref "Q3") (pin "4") (pinfunction "G_4") (pintype "unspecified"))
      (node (ref "R22") (pin "2") (pinfunction "2_2") (pintype "input"))
    )
    (net (code "36") (name "Net-(Q4-G)") (class "Default")
      (node (ref "Q4") (pin "4") (pinfunction "G_4") (pintype "unspecified"))
      (node (ref "R25") (pin "2") (pinfunction "2_2") (pintype "input"))
    )
    (net (code "37") (name "Net-(Q5-G)") (class "Default")
      (node (ref "Q5") (pin "4") (pinfunction "G_4") (pintype "unspecified"))
      (node (ref "R26") (pin "2") (pinfunction "2_2") (pintype "input"))
    )
    (net (code "38") (name "Net-(Q6-G)") (class "Default")
      (node (ref "Q6") (pin "4") (pinfunction "G_4") (pintype "unspecified"))
      (node (ref "R27") (pin "2") (pinfunction "2_2") (pintype "input"))
    )
    (net (code "39") (name "Net-(U1-BOOT)") (class "Default")
      (node (ref "C1") (pin "1") (pinfunction "1_1") (pintype "input"))
      (node (ref "U1") (pin "6") (pinfunction "BOOT_6") (pintype "unspecified"))
    )
    (net (code "40") (name "Net-(U1-EN)") (class "Default")
      (node (ref "R1") (pin "2") (pinfunction "2_2") (pintype "input"))
      (node (ref "U1") (pin "5") (pinfunction "EN_5") (pintype "unspecified"))
    )
    (net (code "41") (name "Net-(U1-FB)") (class "Default")
      (node (ref "R3") (pin "1") (pinfunction "1_1") (pintype "input"))
      (node (ref "R4") (pin "1") (pinfunction "1_1") (pintype "input"))
      (node (ref "U1") (pin "4") (pinfunction "FB_4") (pintype "unspecified"))
    )
    (net (code "42") (name "Net-(U1-SW)") (class "Default")
      (node (ref "C1") (pin "2") (pinfunction "2_2") (pintype "input"))
      (node (ref "L1") (pin "1") (pinfunction "1_1") (pintype "unspecified"))
      (node (ref "U1") (pin "2") (pinfunction "SW_2") (pintype "unspecified"))
    )
    (net (code "43") (name "U") (class "Default")
      (node (ref "C3") (pin "1") (pinfunction "1_1") (pintype "unspecified"))
      (node (ref "Q1") (pin "1") (pinfunction "S_1") (pintype "unspecified"))
      (node (ref "Q1") (pin "2") (pinfunction "S_2") (pintype "unspecified"))
      (node (ref "Q1") (pin "3") (pinfunction "S_3") (pintype "unspecified"))
      (node (ref "Q4") (pin "5") (pinfunction "D_5") (pintype "unspecified"))
      (node (ref "Q4") (pin "6") (pinfunction "D_6") (pintype "unspecified"))
      (node (ref "Q4") (pin "7") (pinfunction "D_7") (pintype "unspecified"))
      (node (ref "Q4") (pin "8") (pinfunction "D_8") (pintype "unspecified"))
      (node (ref "R8") (pin "1") (pinfunction "1_1") (pintype "input"))
      (node (ref "U3") (pin "18") (pinfunction "VS1_18") (pintype "unspecified"))
    )
    (net (code "44") (name "V") (class "Default")
      (node (ref "C8") (pin "1") (pinfunction "1_1") (pintype "unspecified"))
      (node (ref "Q2") (pin "1") (pinfunction "S_1") (pintype "unspecified"))
      (node (ref "Q2") (pin "2") (pinfunction "S_2") (pintype "unspecified"))
      (node (ref "Q2") (pin "3") (pinfunction "S_3") (pintype "unspecified"))
      (node (ref "Q5") (pin "5") (pinfunction "D_5") (pintype "unspecified"))
      (node (ref "Q5") (pin "6") (pinfunction "D_6") (pintype "unspecified"))
      (node (ref "Q5") (pin "7") (pinfunction "D_7") (pintype "unspecified"))
      (node (ref "Q5") (pin "8") (pinfunction "D_8") (pintype "unspecified"))
      (node (ref "R12") (pin "1") (pinfunction "1_1") (pintype "input"))
      (node (ref "U3") (pin "15") (pinfunction "VS2_15") (pintype "unspecified"))
    )
    (net (code "45") (name "VCC3V3") (class "Default")
      (node (ref "C18") (pin "2") (pinfunction "2_2") (pintype "input"))
      (node (ref "C19") (pin "2") (pinfunction "2_2") (pintype "input"))
      (node (ref "C20") (pin "2") (pinfunction "2_2") (pintype "input"))
      (node (ref "C21") (pin "2") (pinfunction "2_2") (pintype "input"))
      (node (ref "C23") (pin "2") (pinfunction "2_2") (pintype "unspecified"))
      (node (ref "R10") (pin "2") (pinfunction "2_2") (pintype "input"))
      (node (ref "R2") (pin "1") (pinfunction "1_1") (pintype "input"))
      (node (ref "R29") (pin "1") (pinfunction "1_1") (pintype "input"))
      (node (ref "R5") (pin "2") (pinfunction "2_2") (pintype "input"))
      (node (ref "R6") (pin "2") (pinfunction "2_2") (pintype "input"))
      (node (ref "R7") (pin "2") (pinfunction "2_2") (pintype "input"))
      (node (ref "U10") (pin "2") (pinfunction "Vout_2") (pintype "unspecified"))
      (node (ref "U4") (pin "24") (pinfunction "VDD_1_24") (pintype "unspecified"))
      (node (ref "U4") (pin "36") (pinfunction "VDD_2_36") (pintype "unspecified"))
      (node (ref "U4") (pin "48") (pinfunction "VDD_3_48") (pintype "unspecified"))
      (node (ref "U4") (pin "9") (pinfunction "VDDA_9") (pintype "unspecified"))
      (node (ref "U6") (pin "1") (pinfunction "1_1") (pintype "input"))
    )
    (net (code "46") (name "VCC5V") (class "Default")
      (node (ref "C10") (pin "1") (pinfunction "1_1") (pintype "unspecified"))
      (node (ref "C22") (pin "1") (pinfunction "1_1") (pintype "unspecified"))
      (node (ref "C9") (pin "1") (pinfunction "1_1") (pintype "unspecified"))
      (node (ref "L1") (pin "2") (pinfunction "2_2") (pintype "unspecified"))
      (node (ref "R3") (pin "2") (pinfunction "2_2") (pintype "input"))
      (node (ref "U10") (pin "3") (pinfunction "Vin_3") (pintype "unspecified"))
    )
    (net (code "47") (name "VCC12V") (class "Default")
      (node (ref "C12") (pin "2") (pinfunction "2_2") (pintype "unspecified"))
      (node (ref "C24") (pin "1") (pinfunction "1_1") (pintype "unspecified"))
      (node (ref "C26") (pin "1") (pinfunction "1_1") (pintype "unspecified"))
      (node (ref "C27") (pin "1") (pinfunction "1_1") (pintype "unspecified"))
      (node (ref "C28") (pin "1") (pinfunction "1_1") (pintype "unspecified"))
      (node (ref "C30") (pin "1") (pinfunction "1_1") (pintype "unspecified"))
      (node (ref "C31") (pin "1") (pinfunction "1_1") (pintype "unspecified"))
      (node (ref "C32") (pin "2") (pinfunction "2_2") (pintype "input"))
      (node (ref "C4") (pin "2") (pinfunction "2_2") (pintype "unspecified"))
      (node (ref "C5") (pin "2") (pinfunction "2_2") (pintype "unspecified"))
      (node (ref "C6") (pin "2") (pinfunction "2_2") (pintype "input"))
      (node (ref "D1") (pin "2") (pinfunction "A_2") (pintype "unspecified"))
      (node (ref "D10") (pin "1") (pinfunction "K_1") (pintype "unspecified"))
      (node (ref "D2") (pin "2") (pinfunction "A_2") (pintype "unspecified"))
      (node (ref "D3") (pin "2") (pinfunction "A_2") (pintype "unspecified"))
      (node (ref "Q1") (pin "5") (pinfunction "D_5") (pintype "unspecified"))
      (node (ref "Q1") (pin "6") (pinfunction "D_6") (pintype "unspecified"))
      (node (ref "Q1") (pin "7") (pinfunction "D_7") (pintype "unspecified"))
      (node (ref "Q1") (pin "8") (pinfunction "D_8") (pintype "unspecified"))
      (node (ref "Q2") (pin "5") (pinfunction "D_5") (pintype "unspecified"))
      (node (ref "Q2") (pin "6") (pinfunction "D_6") (pintype "unspecified"))
      (node (ref "Q2") (pin "7") (pinfunction "D_7") (pintype "unspecified"))
      (node (ref "Q2") (pin "8") (pinfunction "D_8") (pintype "unspecified"))
      (node (ref "Q3") (pin "5") (pinfunction "D_5") (pintype "unspecified"))
      (node (ref "Q3") (pin "6") (pinfunction "D_6") (pintype "unspecified"))
      (node (ref "Q3") (pin "7") (pinfunction "D_7") (pintype "unspecified"))
      (node (ref "Q3") (pin "8") (pinfunction "D_8") (pintype "unspecified"))
      (node (ref "R1") (pin "1") (pinfunction "1_1") (pintype "input"))
      (node (ref "U1") (pin "3") (pinfunction "VIN_3") (pintype "unspecified"))
      (node (ref "U3") (pin "7") (pinfunction "VCC_7") (pintype "unspecified"))
      (node (ref "U5") (pin "3") (pinfunction "VCC+_3") (pintype "unspecified"))
    )
    (net (code "48") (name "W") (class "Default")
      (node (ref "C11") (pin "1") (pinfunction "1_1") (pintype "unspecified"))
      (node (ref "Q3") (pin "1") (pinfunction "S_1") (pintype "unspecified"))
      (node (ref "Q3") (pin "2") (pinfunction "S_2") (pintype "unspecified"))
      (node (ref "Q3") (pin "3") (pinfunction "S_3") (pintype "unspecified"))
      (node (ref "Q6") (pin "5") (pinfunction "D_5") (pintype "unspecified"))
      (node (ref "Q6") (pin "6") (pinfunction "D_6") (pintype "unspecified"))
      (node (ref "Q6") (pin "7") (pinfunction "D_7") (pintype "unspecified"))
      (node (ref "Q6") (pin "8") (pinfunction "D_8") (pintype "unspecified"))
      (node (ref "R14") (pin "1") (pinfunction "1_1") (pintype "input"))
      (node (ref "U3") (pin "12") (pinfunction "VS3_12") (pintype "unspecified"))
    )
    (net (code "49") (name "unconnected-(U4-PA0-WKUP-Pad10)") (class "Default")
      (node (ref "U4") (pin "10") (pinfunction "PA0-WKUP_10") (pintype "unspecified"))
    )
    (net (code "50") (name "unconnected-(U4-PA1-Pad11)") (class "Default")
      (node (ref "U4") (pin "11") (pinfunction "PA1_11") (pintype "unspecified"))
    )
    (net (code "51") (name "unconnected-(U4-PA2-Pad12)") (class "Default")
      (node (ref "U4") (pin "12") (pinfunction "PA2_12") (pintype "unspecified"))
    )
    (net (code "52") (name "unconnected-(U4-PA3-Pad13)") (class "Default")
      (node (ref "U4") (pin "13") (pinfunction "PA3_13") (pintype "unspecified"))
    )
    (net (code "53") (name "unconnected-(U4-PA4-Pad14)") (class "Default")
      (node (ref "U4") (pin "14") (pinfunction "PA4_14") (pintype "unspecified"))
    )
    (net (code "54") (name "unconnected-(U4-PA5-Pad15)") (class "Default")
      (node (ref "U4") (pin "15") (pinfunction "PA5_15") (pintype "unspecified"))
    )
    (net (code "55") (name "unconnected-(U4-PA6-Pad16)") (class "Default")
      (node (ref "U4") (pin "16") (pinfunction "PA6_16") (pintype "unspecified"))
    )
    (net (code "56") (name "unconnected-(U4-PA7-Pad17)") (class "Default")
      (node (ref "U4") (pin "17") (pinfunction "PA7_17") (pintype "unspecified"))
    )
    (net (code "57") (name "unconnected-(U4-PA11-Pad32)") (class "Default")
      (node (ref "U4") (pin "32") (pinfunction "PA11_32") (pintype "unspecified"))
    )
    (net (code "58") (name "unconnected-(U4-PA12-Pad33)") (class "Default")
      (node (ref "U4") (pin "33") (pinfunction "PA12_33") (pintype "unspecified"))
    )
    (net (code "59") (name "unconnected-(U4-PA15-Pad38)") (class "Default")
      (node (ref "U4") (pin "38") (pinfunction "PA15_38") (pintype "unspecified"))
    )
    (net (code "60") (name "unconnected-(U4-PB0-Pad18)") (class "Default")
      (node (ref "U4") (pin "18") (pinfunction "PB0_18") (pintype "unspecified"))
    )
    (net (code "61") (name "unconnected-(U4-PB1-Pad19)") (class "Default")
      (node (ref "U4") (pin "19") (pinfunction "PB1_19") (pintype "unspecified"))
    )
    (net (code "62") (name "unconnected-(U4-PB3-Pad39)") (class "Default")
      (node (ref "U4") (pin "39") (pinfunction "PB3_39") (pintype "unspecified"))
    )
    (net (code "63") (name "unconnected-(U4-PB4-Pad40)") (class "Default")
      (node (ref "U4") (pin "40") (pinfunction "PB4_40") (pintype "unspecified"))
    )
    (net (code "64") (name "unconnected-(U4-PB5-Pad41)") (class "Default")
      (node (ref "U4") (pin "41") (pinfunction "PB5_41") (pintype "unspecified"))
    )
    (net (code "65") (name "unconnected-(U4-PB7-Pad43)") (class "Default")
      (node (ref "U4") (pin "43") (pinfunction "PB7_43") (pintype "unspecified"))
    )
    (net (code "66") (name "unconnected-(U4-PB8-Pad45)") (class "Default")
      (node (ref "U4") (pin "45") (pinfunction "PB8_45") (pintype "unspecified"))
    )
    (net (code "67") (name "unconnected-(U4-PB9-Pad46)") (class "Default")
      (node (ref "U4") (pin "46") (pinfunction "PB9_46") (pintype "unspecified"))
    )
    (net (code "68") (name "unconnected-(U4-PC13-TAMPER-RTC-Pad2)") (class "Default")
      (node (ref "U4") (pin "2") (pinfunction "PC13-TAMPER-RTC_2") (pintype "unspecified"))
    )
    (net (code "69") (name "unconnected-(U4-PC14-OSC32_IN-Pad3)") (class "Default")
      (node (ref "U4") (pin "3") (pinfunction "PC14-OSC32_IN_3") (pintype "unspecified"))
    )
    (net (code "70") (name "unconnected-(U4-PC15-OSC32_OUT-Pad4)") (class "Default")
      (node (ref "U4") (pin "4") (pinfunction "PC15-OSC32_OUT_4") (pintype "unspecified"))
    )
    (net (code "71") (name "unconnected-(U4-VBAT-Pad1)") (class "Default")
      (node (ref "U4") (pin "1") (pinfunction "VBAT_1") (pintype "unspecified"))
    )
    (net (code "72") (name "unconnected-(U5-IN4+-Pad11)") (class "Default")
      (node (ref "U5") (pin "11") (pinfunction "IN4+_11") (pintype "unspecified+no_connect"))
    )
    (net (code "73") (name "unconnected-(U5-IN4--Pad10)") (class "Default")
      (node (ref "U5") (pin "10") (pinfunction "IN4-_10") (pintype "unspecified+no_connect"))
    )
    (net (code "74") (name "unconnected-(U5-OUTPUT4-Pad13)") (class "Default")
      (node (ref "U5") (pin "13") (pinfunction "OUTPUT4_13") (pintype "unspecified+no_connect"))
    )
    (net (code "75") (name "unconnected-(X1-GND-Pad2)") (class "Default")
      (node (ref "X1") (pin "2") (pinfunction "GND_2") (pintype "input"))
    )
    (net (code "76") (name "unconnected-(X1-GND-Pad4)") (class "Default")
      (node (ref "X1") (pin "4") (pinfunction "GND_4") (pintype "input"))
    )
  )
)
